# femtoUSB_r1_0_0_TQFP_BREADBOARD.net
KiCad netlist of a schematic drawn in EAGLE
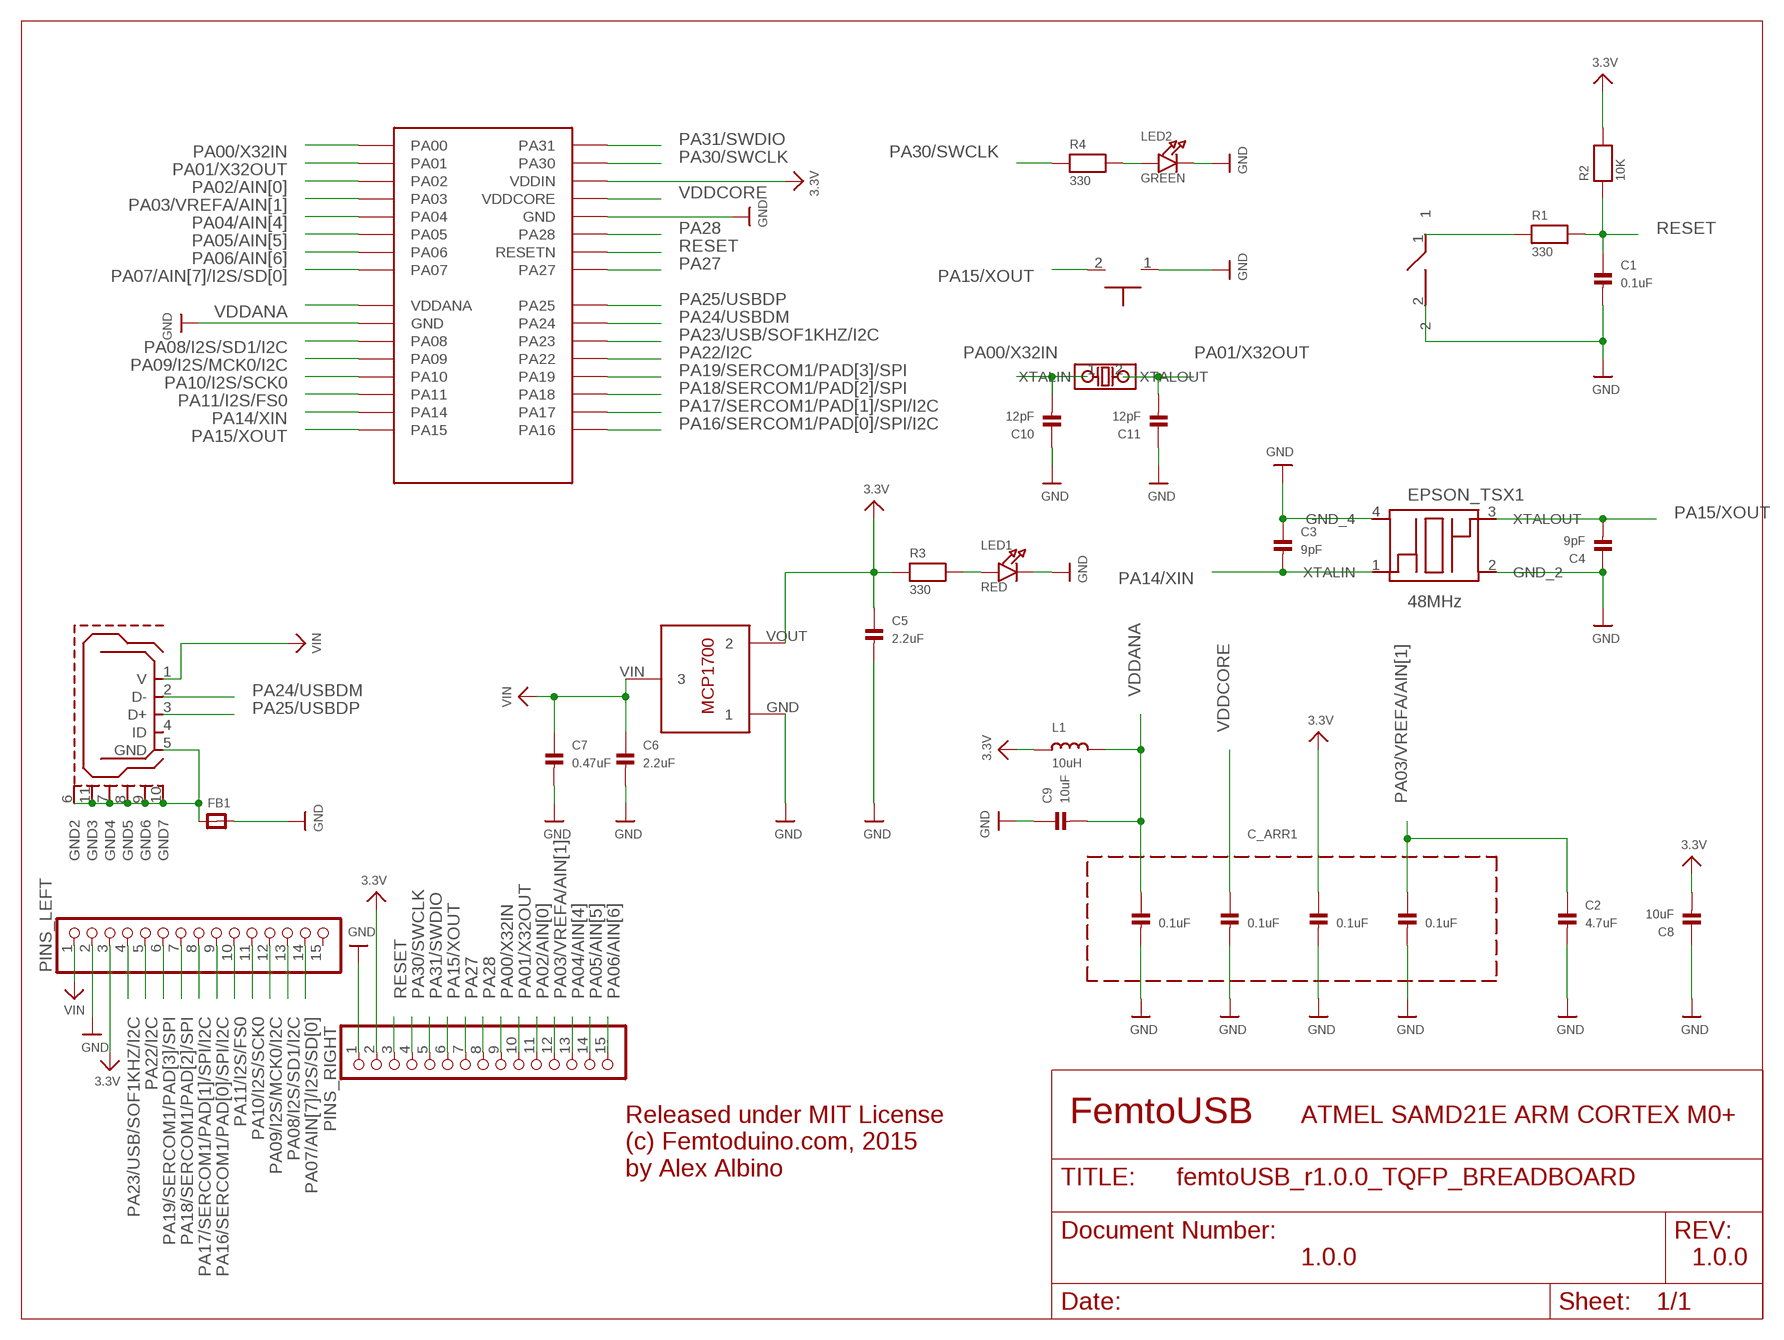
[diagram p0: schematic, sheet 1]

(export (version "E")
  (design (tool "Eeschema 10.0.6"))
  (components
    (comp (ref "BOOT_BTN")
      (value "TACTILE_SWITCH_NO_GND_NO_BOSS")
      (footprint "eagle-import:SIDE_ACT_NO_GND_NO_BOSS")
      (libsource (lib "eagle-import") (part "TACTILE_SWITCH_NO_GND_NO_BOSS"))
    )
    (comp (ref "BTN")
      (value "OMRON B3U-300P(M)")
      (footprint "eagle-import:SPST_SMD")
      (libsource (lib "eagle-import") (part "SPST_SMD"))
    )
    (comp (ref "C1")
      (value "0.1uF")
      (footprint "eagle-import:_0402MP")
      (fields (field (name "DIGIKEY_PART") "445-4958-1-ND"))
      (libsource (lib "eagle-import") (part "CAP_CERAMIC_0402MP"))
    )
    (comp (ref "C2")
      (value "4.7uF")
      (footprint "eagle-import:_0402MP")
      (libsource (lib "eagle-import") (part "CAP_CERAMIC_0402MP"))
    )
    (comp (ref "C3")
      (value "9pF")
      (footprint "eagle-import:_0402MP")
      (libsource (lib "eagle-import") (part "CAP_CERAMIC_0402MP"))
    )
    (comp (ref "C4")
      (value "9pF")
      (footprint "eagle-import:_0402MP")
      (libsource (lib "eagle-import") (part "CAP_CERAMIC_0402MP"))
    )
    (comp (ref "C5")
      (value "2.2uF")
      (footprint "eagle-import:_0402MP")
      (libsource (lib "eagle-import") (part "CAP_CERAMIC_0402MP"))
    )
    (comp (ref "C6")
      (value "2.2uF")
      (footprint "eagle-import:_0402MP")
      (libsource (lib "eagle-import") (part "CAP_CERAMIC_0402MP"))
    )
    (comp (ref "C7")
      (value "0.47uF")
      (footprint "eagle-import:_0402MP")
      (libsource (lib "eagle-import") (part "CAP_CERAMIC_0402MP"))
    )
    (comp (ref "C8")
      (value "10uF")
      (footprint "eagle-import:_0402MP")
      (libsource (lib "eagle-import") (part "CAP_CERAMIC_0402MP"))
    )
    (comp (ref "C9")
      (value "10uF")
      (footprint "eagle-import:_0402MP")
      (libsource (lib "eagle-import") (part "CAP_CERAMIC_0402MP"))
    )
    (comp (ref "C10")
      (value "12pF")
      (footprint "eagle-import:_0402MP")
      (libsource (lib "eagle-import") (part "CAP_CERAMIC_0402MP"))
    )
    (comp (ref "C11")
      (value "12pF")
      (footprint "eagle-import:_0402MP")
      (libsource (lib "eagle-import") (part "CAP_CERAMIC_0402MP"))
    )
    (comp (ref "C_ARR1")
      (value "0.1uF")
      (footprint "eagle-import:CAPACITOR_ARRAY_1206_MONO_1X4")
      (libsource (lib "eagle-import") (part "KEMET_CERAMIC_CAPACITOR_ARRAY_1X4"))
    )
    (comp (ref "EPSON_TSX1")
      (value "48MHz")
      (footprint "eagle-import:TSX-3225")
      (fields (field (name "DIGIKEY_PART") "TSX-3225 32.0000MF15X-B-ND"))
      (libsource (lib "eagle-import") (part "TSX-3225"))
    )
    (comp (ref "FB1")
      (value "FERRITE_0603MP")
      (footprint "eagle-import:_0603MP")
      (libsource (lib "eagle-import") (part "FERRITE_0603MP"))
    )
    (comp (ref "IC1")
      (value "ATSAMD21E18A-AU")
      (footprint "eagle-import:32-TQFP")
      (fields (field (name "DIGIKEY_PART") "ATSAMD21E18A-AU-ND"))
      (libsource (lib "eagle-import") (part "ATSAMD21E18A-AU"))
    )
    (comp (ref "L1")
      (value "10uH")
      (footprint "eagle-import:_0603MP")
      (libsource (lib "eagle-import") (part "INDUCTOR_0603MP"))
    )
    (comp (ref "LDO_VREG")
      (value "MCP1700T-3302E/TT")
      (footprint "eagle-import:MCP1700T-3302E_TT")
      (libsource (lib "eagle-import") (part "MCP1700T-3302E/TT"))
    )
    (comp (ref "LED1")
      (value "RED")
      (footprint "eagle-import:CHIPLED_0603_NOOUTLINE")
      (libsource (lib "eagle-import") (part "LED0603_NOOUTLINE"))
    )
    (comp (ref "LED2")
      (value "GREEN")
      (footprint "eagle-import:CHIPLED_0603_NOOUTLINE")
      (libsource (lib "eagle-import") (part "LED0603_NOOUTLINE"))
    )
    (comp (ref "MICRO_B_USB")
      (value "USB_MICROB")
      (footprint "eagle-import:USB_MICROB_PACKAGE")
      (libsource (lib "eagle-import") (part "USB_MICROB"))
    )
    (comp (ref "PINS_LEFT")
      (value "HEADER-1X15")
      (footprint "eagle-import:1X15_ROUND_70")
      (libsource (lib "eagle-import") (part "HEADER-1X15"))
    )
    (comp (ref "PINS_RIGHT")
      (value "HEADER-1X15")
      (footprint "eagle-import:1X15_ROUND_70")
      (libsource (lib "eagle-import") (part "HEADER-1X15"))
    )
    (comp (ref "R1")
      (value "330")
      (footprint "eagle-import:_0402MP")
      (fields (field (name "DIGIKEY_PART") "541-330JCT-ND"))
      (libsource (lib "eagle-import") (part "RESISTOR_0402MP"))
    )
    (comp (ref "R2")
      (value "10K")
      (footprint "eagle-import:_0402MP")
      (libsource (lib "eagle-import") (part "RESISTOR_0402MP"))
    )
    (comp (ref "R3")
      (value "330")
      (footprint "eagle-import:_0402MP")
      (libsource (lib "eagle-import") (part "RESISTOR_0402MP"))
    )
    (comp (ref "R4")
      (value "330")
      (footprint "eagle-import:_0402MP")
      (libsource (lib "eagle-import") (part "RESISTOR_0402MP"))
    )
    (comp (ref "U$40")
      (value "ABS06-107-32.768KHZ-T")
      (footprint "eagle-import:ABS06-107-32.768KHZ-T")
      (libsource (lib "eagle-import") (part "ABS06-107-32.768KHZ-T"))
    )
  )
  (nets
    (net (code "1") (name "/PA00{slash}X32IN") (class "Default")
      (node (ref "C10") (pin "2") (pinfunction "P$2_2") (pintype "passive"))
      (node (ref "IC1") (pin "1") (pinfunction "PA00_1") (pintype "bidirectional"))
      (node (ref "PINS_RIGHT") (pin "9") (pinfunction "9_9") (pintype "passive"))
      (node (ref "U$40") (pin "1") (pinfunction "XTALIN_1") (pintype "bidirectional"))
    )
    (net (code "2") (name "/PA01{slash}X32OUT") (class "Default")
      (node (ref "C11") (pin "2") (pinfunction "P$2_2") (pintype "passive"))
      (node (ref "IC1") (pin "2") (pinfunction "PA01_2") (pintype "bidirectional"))
      (node (ref "PINS_RIGHT") (pin "10") (pinfunction "10_10") (pintype "passive"))
      (node (ref "U$40") (pin "2") (pinfunction "XTALOUT_2") (pintype "bidirectional"))
    )
    (net (code "3") (name "/PA02{slash}AIN[0]") (class "Default")
      (node (ref "IC1") (pin "3") (pinfunction "PA02_3") (pintype "bidirectional"))
      (node (ref "PINS_RIGHT") (pin "11") (pinfunction "11_11") (pintype "passive"))
    )
    (net (code "4") (name "/PA03{slash}VREFA{slash}AIN[1]") (class "Default")
      (node (ref "C2") (pin "1") (pinfunction "P$1_1") (pintype "passive"))
      (node (ref "C_ARR1") (pin "7") (pinfunction "P$7_7") (pintype "passive"))
      (node (ref "IC1") (pin "4") (pinfunction "PA03_4") (pintype "bidirectional"))
      (node (ref "PINS_RIGHT") (pin "12") (pinfunction "12_12") (pintype "passive"))
    )
    (net (code "5") (name "/PA04{slash}AIN[4]") (class "Default")
      (node (ref "IC1") (pin "5") (pinfunction "PA04_5") (pintype "bidirectional"))
      (node (ref "PINS_RIGHT") (pin "13") (pinfunction "13_13") (pintype "passive"))
    )
    (net (code "6") (name "/PA05{slash}AIN[5]") (class "Default")
      (node (ref "IC1") (pin "6") (pinfunction "PA05_6") (pintype "bidirectional"))
      (node (ref "PINS_RIGHT") (pin "14") (pinfunction "14_14") (pintype "passive"))
    )
    (net (code "7") (name "/PA06{slash}AIN[6]") (class "Default")
      (node (ref "IC1") (pin "7") (pinfunction "PA06_7") (pintype "bidirectional"))
      (node (ref "PINS_RIGHT") (pin "15") (pinfunction "15_15") (pintype "passive"))
    )
    (net (code "8") (name "/PA07{slash}AIN[7]{slash}I2S{slash}SD[0]") (class "Default")
      (node (ref "IC1") (pin "8") (pinfunction "PA07_8") (pintype "bidirectional"))
      (node (ref "PINS_LEFT") (pin "14") (pinfunction "14_14") (pintype "passive"))
    )
    (net (code "9") (name "/PA08{slash}I2S{slash}SD1{slash}I2C") (class "Default")
      (node (ref "IC1") (pin "11") (pinfunction "PA08_11") (pintype "bidirectional"))
      (node (ref "PINS_LEFT") (pin "13") (pinfunction "13_13") (pintype "passive"))
    )
    (net (code "10") (name "/PA09{slash}I2S{slash}MCK0{slash}I2C") (class "Default")
      (node (ref "IC1") (pin "12") (pinfunction "PA09_12") (pintype "bidirectional"))
      (node (ref "PINS_LEFT") (pin "12") (pinfunction "12_12") (pintype "passive"))
    )
    (net (code "11") (name "/PA10{slash}I2S{slash}SCK0") (class "Default")
      (node (ref "IC1") (pin "13") (pinfunction "PA10_13") (pintype "bidirectional"))
      (node (ref "PINS_LEFT") (pin "11") (pinfunction "11_11") (pintype "passive"))
    )
    (net (code "12") (name "/PA11{slash}I2S{slash}FS0") (class "Default")
      (node (ref "IC1") (pin "14") (pinfunction "PA11_14") (pintype "bidirectional"))
      (node (ref "PINS_LEFT") (pin "10") (pinfunction "10_10") (pintype "passive"))
    )
    (net (code "13") (name "/PA14{slash}XIN") (class "Default")
      (node (ref "C3") (pin "2") (pinfunction "P$2_2") (pintype "passive"))
      (node (ref "EPSON_TSX1") (pin "1") (pinfunction "XTALIN_1") (pintype "bidirectional"))
      (node (ref "IC1") (pin "15") (pinfunction "PA14_15") (pintype "bidirectional"))
    )
    (net (code "14") (name "/PA15{slash}XOUT") (class "Default")
      (node (ref "BOOT_BTN") (pin "2") (pinfunction "2_2") (pintype "bidirectional"))
      (node (ref "C4") (pin "2") (pinfunction "P$2_2") (pintype "passive"))
      (node (ref "EPSON_TSX1") (pin "3") (pinfunction "XTALOUT_3") (pintype "bidirectional"))
      (node (ref "IC1") (pin "16") (pinfunction "PA15_16") (pintype "bidirectional"))
      (node (ref "PINS_RIGHT") (pin "6") (pinfunction "6_6") (pintype "passive"))
    )
    (net (code "15") (name "/PA16{slash}SERCOM1{slash}PAD[0]{slash}SPI{slash}I2C") (class "Default")
      (node (ref "IC1") (pin "17") (pinfunction "PA16_17") (pintype "bidirectional"))
      (node (ref "PINS_LEFT") (pin "9") (pinfunction "9_9") (pintype "passive"))
    )
    (net (code "16") (name "/PA17{slash}SERCOM1{slash}PAD[1]{slash}SPI{slash}I2C") (class "Default")
      (node (ref "IC1") (pin "18") (pinfunction "PA17_18") (pintype "bidirectional"))
      (node (ref "PINS_LEFT") (pin "8") (pinfunction "8_8") (pintype "passive"))
    )
    (net (code "17") (name "/PA18{slash}SERCOM1{slash}PAD[2]{slash}SPI") (class "Default")
      (node (ref "IC1") (pin "19") (pinfunction "PA18_19") (pintype "bidirectional"))
      (node (ref "PINS_LEFT") (pin "7") (pinfunction "7_7") (pintype "passive"))
    )
    (net (code "18") (name "/PA19{slash}SERCOM1{slash}PAD[3]{slash}SPI") (class "Default")
      (node (ref "IC1") (pin "20") (pinfunction "PA19_20") (pintype "bidirectional"))
      (node (ref "PINS_LEFT") (pin "6") (pinfunction "6_6") (pintype "passive"))
    )
    (net (code "19") (name "/PA22{slash}I2C") (class "Default")
      (node (ref "IC1") (pin "21") (pinfunction "PA22_21") (pintype "bidirectional"))
      (node (ref "PINS_LEFT") (pin "5") (pinfunction "5_5") (pintype "passive"))
    )
    (net (code "20") (name "/PA23{slash}USB{slash}SOF1KHZ{slash}I2C") (class "Default")
      (node (ref "IC1") (pin "22") (pinfunction "PA23_22") (pintype "bidirectional"))
      (node (ref "PINS_LEFT") (pin "4") (pinfunction "4_4") (pintype "passive"))
    )
    (net (code "21") (name "/PA24{slash}USBDM") (class "Default")
      (node (ref "IC1") (pin "23") (pinfunction "PA24_23") (pintype "bidirectional"))
      (node (ref "MICRO_B_USB") (pin "2") (pinfunction "D-_2") (pintype "bidirectional"))
    )
    (net (code "22") (name "/PA25{slash}USBDP") (class "Default")
      (node (ref "IC1") (pin "24") (pinfunction "PA25_24") (pintype "bidirectional"))
      (node (ref "MICRO_B_USB") (pin "3") (pinfunction "D+_3") (pintype "bidirectional"))
    )
    (net (code "23") (name "/PA27") (class "Default")
      (node (ref "IC1") (pin "25") (pinfunction "PA27_25") (pintype "bidirectional"))
      (node (ref "PINS_RIGHT") (pin "7") (pinfunction "7_7") (pintype "passive"))
    )
    (net (code "24") (name "/PA28") (class "Default")
      (node (ref "IC1") (pin "27") (pinfunction "PA28_27") (pintype "bidirectional"))
      (node (ref "PINS_RIGHT") (pin "8") (pinfunction "8_8") (pintype "passive"))
    )
    (net (code "25") (name "/PA30{slash}SWCLK") (class "Default")
      (node (ref "IC1") (pin "31") (pinfunction "PA30_31") (pintype "bidirectional"))
      (node (ref "PINS_RIGHT") (pin "4") (pinfunction "4_4") (pintype "passive"))
      (node (ref "R4") (pin "1") (pinfunction "1_1") (pintype "passive"))
    )
    (net (code "26") (name "/PA31{slash}SWDIO") (class "Default")
      (node (ref "IC1") (pin "32") (pinfunction "PA31_32") (pintype "bidirectional"))
      (node (ref "PINS_RIGHT") (pin "5") (pinfunction "5_5") (pintype "passive"))
    )
    (net (code "27") (name "/RESET") (class "Default")
      (node (ref "C1") (pin "1") (pinfunction "P$1_1") (pintype "passive"))
      (node (ref "IC1") (pin "26") (pinfunction "RESETN_26") (pintype "bidirectional"))
      (node (ref "PINS_RIGHT") (pin "3") (pinfunction "3_3") (pintype "passive"))
      (node (ref "R1") (pin "2") (pinfunction "2_2") (pintype "passive"))
      (node (ref "R2") (pin "1") (pinfunction "1_1") (pintype "passive"))
    )
    (net (code "28") (name "/VDDANA") (class "Default")
      (node (ref "C9") (pin "2") (pinfunction "P$2_2") (pintype "passive"))
      (node (ref "C_ARR1") (pin "1") (pinfunction "P$1_1") (pintype "passive"))
      (node (ref "IC1") (pin "9") (pinfunction "VDDANA_9") (pintype "bidirectional"))
      (node (ref "L1") (pin "2") (pinfunction "2_2") (pintype "passive"))
    )
    (net (code "29") (name "/VDDCORE") (class "Default")
      (node (ref "C_ARR1") (pin "3") (pinfunction "P$3_3") (pintype "passive"))
      (node (ref "IC1") (pin "29") (pinfunction "VDDCORE_29") (pintype "bidirectional"))
    )
    (net (code "30") (name "3.3V") (class "Default")
      (node (ref "C5") (pin "1") (pinfunction "P$1_1") (pintype "passive"))
      (node (ref "C8") (pin "2") (pinfunction "P$2_2") (pintype "passive"))
      (node (ref "C_ARR1") (pin "5") (pinfunction "P$5_5") (pintype "passive"))
      (node (ref "IC1") (pin "30") (pinfunction "VDDIN_30") (pintype "bidirectional"))
      (node (ref "L1") (pin "1") (pinfunction "1_1") (pintype "passive"))
      (node (ref "LDO_VREG") (pin "VOUT") (pinfunction "2_VOUT") (pintype "bidirectional"))
      (node (ref "PINS_LEFT") (pin "3") (pinfunction "3_3") (pintype "passive"))
      (node (ref "PINS_RIGHT") (pin "2") (pinfunction "2_2") (pintype "passive"))
      (node (ref "R2") (pin "2") (pinfunction "2_2") (pintype "passive"))
      (node (ref "R3") (pin "1") (pinfunction "1_1") (pintype "passive"))
    )
    (net (code "31") (name "GND") (class "Default")
      (node (ref "BOOT_BTN") (pin "1") (pinfunction "1_1") (pintype "bidirectional"))
      (node (ref "BTN") (pin "2") (pinfunction "2_2") (pintype "bidirectional"))
      (node (ref "C1") (pin "2") (pinfunction "P$2_2") (pintype "passive"))
      (node (ref "C10") (pin "1") (pinfunction "P$1_1") (pintype "passive"))
      (node (ref "C11") (pin "1") (pinfunction "P$1_1") (pintype "passive"))
      (node (ref "C2") (pin "2") (pinfunction "P$2_2") (pintype "passive"))
      (node (ref "C3") (pin "1") (pinfunction "P$1_1") (pintype "passive"))
      (node (ref "C4") (pin "1") (pinfunction "P$1_1") (pintype "passive"))
      (node (ref "C5") (pin "2") (pinfunction "P$2_2") (pintype "passive"))
      (node (ref "C6") (pin "2") (pinfunction "P$2_2") (pintype "passive"))
      (node (ref "C7") (pin "2") (pinfunction "P$2_2") (pintype "passive"))
      (node (ref "C8") (pin "1") (pinfunction "P$1_1") (pintype "passive"))
      (node (ref "C9") (pin "1") (pinfunction "P$1_1") (pintype "passive"))
      (node (ref "C_ARR1") (pin "2") (pinfunction "P$2_2") (pintype "passive"))
      (node (ref "C_ARR1") (pin "4") (pinfunction "P$4_4") (pintype "passive"))
      (node (ref "C_ARR1") (pin "6") (pinfunction "P$6_6") (pintype "passive"))
      (node (ref "C_ARR1") (pin "8") (pinfunction "P$8_8") (pintype "passive"))
      (node (ref "EPSON_TSX1") (pin "2") (pinfunction "GND_2_2") (pintype "bidirectional"))
      (node (ref "EPSON_TSX1") (pin "4") (pinfunction "GND_4_4") (pintype "bidirectional"))
      (node (ref "FB1") (pin "2") (pinfunction "P$2_2") (pintype "passive"))
      (node (ref "IC1") (pin "10") (pinfunction "GND_10") (pintype "bidirectional"))
      (node (ref "IC1") (pin "28") (pinfunction "GND_28") (pintype "bidirectional"))
      (node (ref "LDO_VREG") (pin "GND") (pinfunction "1_GND") (pintype "bidirectional"))
      (node (ref "LED1") (pin "C") (pinfunction "C_C") (pintype "passive"))
      (node (ref "LED2") (pin "C") (pinfunction "C_C") (pintype "passive"))
      (node (ref "PINS_LEFT") (pin "2") (pinfunction "2_2") (pintype "passive"))
      (node (ref "PINS_RIGHT") (pin "1") (pinfunction "1_1") (pintype "passive"))
    )
    (net (code "32") (name "Net-(BTN-Pad1)") (class "Default")
      (node (ref "BTN") (pin "1") (pinfunction "1_1") (pintype "bidirectional"))
      (node (ref "R1") (pin "1") (pinfunction "1_1") (pintype "passive"))
    )
    (net (code "33") (name "Net-(FB1-P$1)") (class "Default")
      (node (ref "FB1") (pin "1") (pinfunction "P$1_1") (pintype "passive"))
      (node (ref "MICRO_B_USB") (pin "10") (pinfunction "GND7_10") (pintype "bidirectional"))
      (node (ref "MICRO_B_USB") (pin "11") (pinfunction "GND3_11") (pintype "bidirectional"))
      (node (ref "MICRO_B_USB") (pin "5") (pinfunction "GND_5") (pintype "bidirectional"))
      (node (ref "MICRO_B_USB") (pin "6") (pinfunction "GND2_6") (pintype "bidirectional"))
      (node (ref "MICRO_B_USB") (pin "7") (pinfunction "GND4_7") (pintype "bidirectional"))
      (node (ref "MICRO_B_USB") (pin "8") (pinfunction "GND5_8") (pintype "bidirectional"))
      (node (ref "MICRO_B_USB") (pin "9") (pinfunction "GND6_9") (pintype "bidirectional"))
    )
    (net (code "34") (name "Net-(LED1-PadA)") (class "Default")
      (node (ref "LED1") (pin "A") (pinfunction "A_A") (pintype "passive"))
      (node (ref "R3") (pin "2") (pinfunction "2_2") (pintype "passive"))
    )
    (net (code "35") (name "Net-(LED2-PadA)") (class "Default")
      (node (ref "LED2") (pin "A") (pinfunction "A_A") (pintype "passive"))
      (node (ref "R4") (pin "2") (pinfunction "2_2") (pintype "passive"))
    )
    (net (code "36") (name "VIN") (class "Default")
      (node (ref "C6") (pin "1") (pinfunction "P$1_1") (pintype "passive"))
      (node (ref "C7") (pin "1") (pinfunction "P$1_1") (pintype "passive"))
      (node (ref "LDO_VREG") (pin "VIN") (pinfunction "3_VIN") (pintype "bidirectional"))
      (node (ref "MICRO_B_USB") (pin "1") (pinfunction "V_1") (pintype "bidirectional"))
      (node (ref "PINS_LEFT") (pin "1") (pinfunction "1_1") (pintype "passive"))
    )
    (net (code "37") (name "unconnected-(MICRO_B_USB-ID-Pad4)") (class "Default")
      (node (ref "MICRO_B_USB") (pin "4") (pinfunction "ID_4") (pintype "bidirectional"))
    )
    (net (code "38") (name "unconnected-(PINS_LEFT-Pad15)") (class "Default")
      (node (ref "PINS_LEFT") (pin "15") (pinfunction "15_15") (pintype "passive"))
    )
  )
)
